# sandh.net
KiCad netlist of a schematic drawn in EAGLE
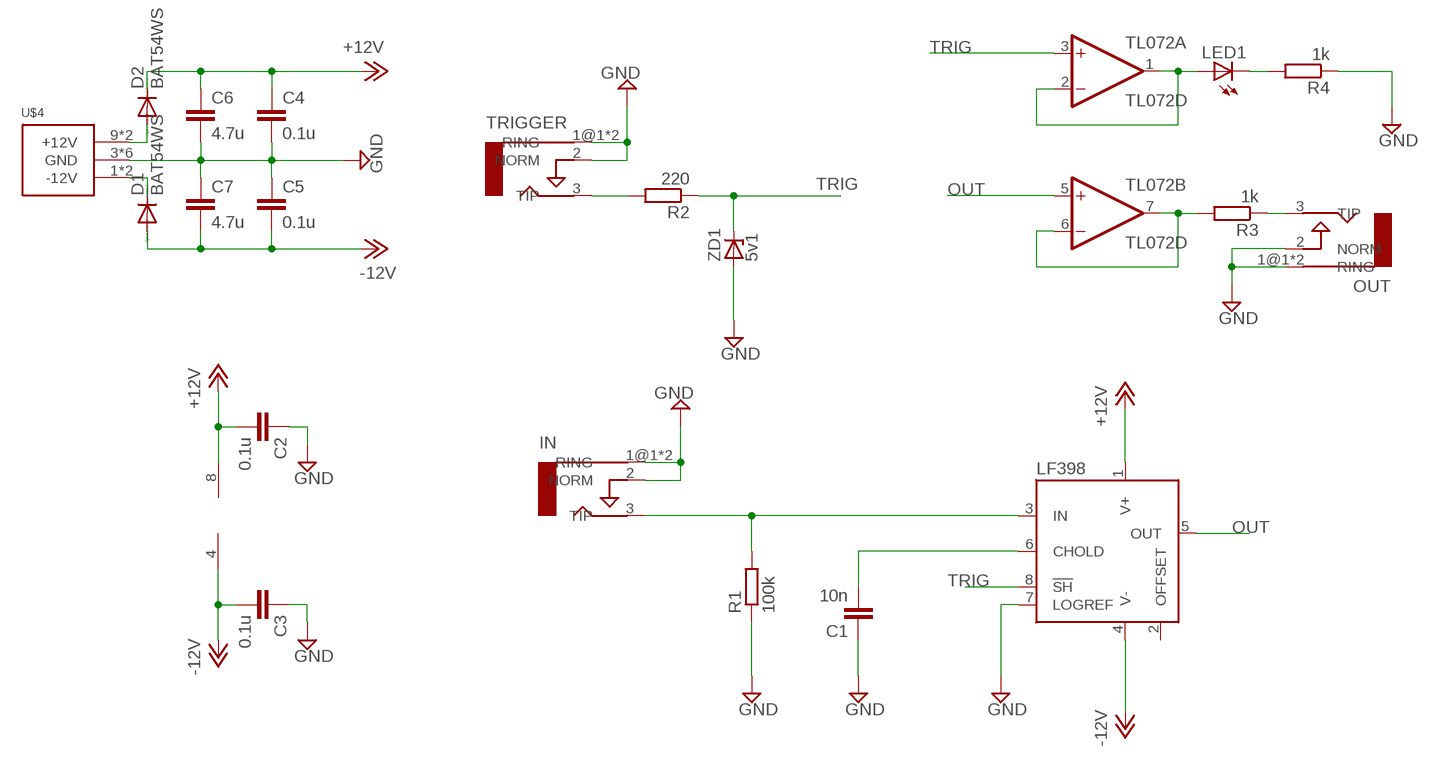
[diagram p0: schematic, sheet 1]

(export (version "E")
  (design (tool "Eeschema 10.0.6"))
  (components
    (comp (ref "C1")
      (value "10n")
      (footprint "eagle-import:C0805")
      (libsource (lib "eagle-import") (part "C-EUC0805"))
    )
    (comp (ref "C2")
      (value "0.1u")
      (footprint "eagle-import:C0805")
      (libsource (lib "eagle-import") (part "C-EUC0805"))
    )
    (comp (ref "C3")
      (value "0.1u")
      (footprint "eagle-import:C0805")
      (libsource (lib "eagle-import") (part "C-EUC0805"))
    )
    (comp (ref "C4")
      (value "0.1u")
      (footprint "eagle-import:C0805")
      (libsource (lib "eagle-import") (part "C-EUC0805"))
    )
    (comp (ref "C5")
      (value "0.1u")
      (footprint "eagle-import:C0805")
      (libsource (lib "eagle-import") (part "C-EUC0805"))
    )
    (comp (ref "C6")
      (value "4.7u")
      (footprint "eagle-import:C0805")
      (libsource (lib "eagle-import") (part "C-EUC0805"))
    )
    (comp (ref "C7")
      (value "4.7u")
      (footprint "eagle-import:C0805")
      (libsource (lib "eagle-import") (part "C-EUC0805"))
    )
    (comp (ref "D1")
      (value "BAT54WS")
      (footprint "eagle-import:SOD323-W")
      (libsource (lib "eagle-import") (part "DIODE-SOD323-W"))
    )
    (comp (ref "D2")
      (value "BAT54WS")
      (footprint "eagle-import:SOD323-W")
      (libsource (lib "eagle-import") (part "DIODE-SOD323-W"))
    )
    (comp (ref "IN")
      (value "AUDIO-JACKERTHENVAR")
      (footprint "eagle-import:ERTHENVAR-JACK")
      (libsource (lib "eagle-import") (part "AUDIO-JACKERTHENVAR"))
    )
    (comp (ref "LED1")
      (value "LEDCHIP-LED0805")
      (footprint "eagle-import:CHIP-LED0805")
      (libsource (lib "eagle-import") (part "LEDCHIP-LED0805"))
    )
    (comp (ref "LF398")
      (value "LF398AN")
      (footprint "eagle-import:DIL08")
      (libsource (lib "eagle-import") (part "LF398AN"))
    )
    (comp (ref "OUT")
      (value "AUDIO-JACKERTHENVAR")
      (footprint "eagle-import:ERTHENVAR-JACK")
      (libsource (lib "eagle-import") (part "AUDIO-JACKERTHENVAR"))
    )
    (comp (ref "R1")
      (value "100k")
      (footprint "eagle-import:R0805")
      (libsource (lib "eagle-import") (part "R-EU_R0805"))
    )
    (comp (ref "R2")
      (value "220")
      (footprint "eagle-import:R0805")
      (libsource (lib "eagle-import") (part "R-EU_R0805"))
    )
    (comp (ref "R3")
      (value "1k")
      (footprint "eagle-import:R0805")
      (libsource (lib "eagle-import") (part "R-EU_R0805"))
    )
    (comp (ref "R4")
      (value "1k")
      (footprint "eagle-import:R0805")
      (libsource (lib "eagle-import") (part "R-EU_R0805"))
    )
    (comp (ref "TL072")
      (value "TL072D")
      (footprint "eagle-import:SO08")
      (libsource (lib "eagle-import") (part "TL072D"))
    )
    (comp (ref "TRIGGER")
      (value "AUDIO-JACKERTHENVAR")
      (footprint "eagle-import:ERTHENVAR-JACK")
      (libsource (lib "eagle-import") (part "AUDIO-JACKERTHENVAR"))
    )
    (comp (ref "U$4")
      (value "POWER_SIMPLE10")
      (footprint "eagle-import:POWER_10")
      (libsource (lib "eagle-import") (part "POWER_SIMPLE10"))
    )
    (comp (ref "ZD1")
      (value "5v1")
      (footprint "eagle-import:ZDIO-2.5")
      (libsource (lib "eagle-import") (part "ZENER-DIODEZD-2.5"))
    )
  )
  (nets
    (net (code "1") (name "+12V") (class "Default")
      (node (ref "C2") (pin "2") (pinfunction "2_2") (pintype "passive"))
      (node (ref "C4") (pin "1") (pinfunction "1_1") (pintype "passive"))
      (node (ref "C6") (pin "1") (pinfunction "1_1") (pintype "passive"))
      (node (ref "D2") (pin "C") (pinfunction "C_C") (pintype "passive"))
      (node (ref "LF398") (pin "1") (pinfunction "V+_1") (pintype "power_in"))
      (node (ref "TL072") (pin "8") (pinfunction "V+_8") (pintype "power_in"))
    )
    (net (code "2") (name "-12V") (class "Default")
      (node (ref "C3") (pin "2") (pinfunction "2_2") (pintype "passive"))
      (node (ref "C5") (pin "2") (pinfunction "2_2") (pintype "passive"))
      (node (ref "C7") (pin "2") (pinfunction "2_2") (pintype "passive"))
      (node (ref "D1") (pin "A") (pinfunction "A_A") (pintype "passive"))
      (node (ref "LF398") (pin "4") (pinfunction "V-_4") (pintype "power_in"))
      (node (ref "TL072") (pin "4") (pinfunction "V-_4") (pintype "power_in"))
    )
    (net (code "3") (name "/OUT") (class "Default")
      (node (ref "LF398") (pin "5") (pinfunction "OUT_5") (pintype "output"))
      (node (ref "TL072") (pin "5") (pinfunction "+IN_5") (pintype "input"))
    )
    (net (code "4") (name "/TRIG") (class "Default")
      (node (ref "LF398") (pin "8") (pinfunction "~{SH}_8") (pintype "input"))
      (node (ref "R2") (pin "1") (pinfunction "1_1") (pintype "passive"))
      (node (ref "TL072") (pin "3") (pinfunction "+IN_3") (pintype "input"))
      (node (ref "ZD1") (pin "C") (pinfunction "C_C") (pintype "passive"))
    )
    (net (code "5") (name "GND") (class "Default")
      (node (ref "C1") (pin "1") (pinfunction "1_1") (pintype "passive"))
      (node (ref "C2") (pin "1") (pinfunction "1_1") (pintype "passive"))
      (node (ref "C3") (pin "1") (pinfunction "1_1") (pintype "passive"))
      (node (ref "C4") (pin "2") (pinfunction "2_2") (pintype "passive"))
      (node (ref "C5") (pin "1") (pinfunction "1_1") (pintype "passive"))
      (node (ref "C6") (pin "2") (pinfunction "2_2") (pintype "passive"))
      (node (ref "C7") (pin "1") (pinfunction "1_1") (pintype "passive"))
      (node (ref "IN") (pin "1@1") (pinfunction "RING_1@1") (pintype "bidirectional"))
      (node (ref "IN") (pin "1@2") (pinfunction "RING_1@2") (pintype "bidirectional"))
      (node (ref "IN") (pin "2") (pinfunction "NORM_2") (pintype "bidirectional"))
      (node (ref "LF398") (pin "7") (pinfunction "LOGREF_7") (pintype "power_in"))
      (node (ref "OUT") (pin "1@1") (pinfunction "RING_1@1") (pintype "bidirectional"))
      (node (ref "OUT") (pin "1@2") (pinfunction "RING_1@2") (pintype "bidirectional"))
      (node (ref "OUT") (pin "2") (pinfunction "NORM_2") (pintype "bidirectional"))
      (node (ref "R1") (pin "1") (pinfunction "1_1") (pintype "passive"))
      (node (ref "R4") (pin "1") (pinfunction "1_1") (pintype "passive"))
      (node (ref "TRIGGER") (pin "1@1") (pinfunction "RING_1@1") (pintype "bidirectional"))
      (node (ref "TRIGGER") (pin "1@2") (pinfunction "RING_1@2") (pintype "bidirectional"))
      (node (ref "TRIGGER") (pin "2") (pinfunction "NORM_2") (pintype "bidirectional"))
      (node (ref "U$4") (pin "3") (pinfunction "GND_3") (pintype "bidirectional"))
      (node (ref "U$4") (pin "4") (pinfunction "GND_4") (pintype "bidirectional"))
      (node (ref "U$4") (pin "5") (pinfunction "GND_5") (pintype "bidirectional"))
      (node (ref "U$4") (pin "6") (pinfunction "GND_6") (pintype "bidirectional"))
      (node (ref "U$4") (pin "7") (pinfunction "GND_7") (pintype "bidirectional"))
      (node (ref "U$4") (pin "8") (pinfunction "GND_8") (pintype "bidirectional"))
      (node (ref "ZD1") (pin "A") (pinfunction "A_A") (pintype "passive"))
    )
    (net (code "6") (name "Net-(D1-PadC)") (class "Default")
      (node (ref "D1") (pin "C") (pinfunction "C_C") (pintype "passive"))
      (node (ref "U$4") (pin "1") (pinfunction "-12V_1") (pintype "bidirectional"))
      (node (ref "U$4") (pin "2") (pinfunction "-12V_2") (pintype "bidirectional"))
    )
    (net (code "7") (name "Net-(D2-PadA)") (class "Default")
      (node (ref "D2") (pin "A") (pinfunction "A_A") (pintype "passive"))
      (node (ref "U$4") (pin "10") (pinfunction "+12V_10") (pintype "bidirectional"))
      (node (ref "U$4") (pin "9") (pinfunction "+12V_9") (pintype "bidirectional"))
    )
    (net (code "8") (name "Net-(IN-TIP)") (class "Default")
      (node (ref "IN") (pin "3") (pinfunction "TIP_3") (pintype "bidirectional"))
      (node (ref "LF398") (pin "3") (pinfunction "IN_3") (pintype "input"))
      (node (ref "R1") (pin "2") (pinfunction "2_2") (pintype "passive"))
    )
    (net (code "9") (name "Net-(LED1-PadC)") (class "Default")
      (node (ref "LED1") (pin "C") (pinfunction "C_C") (pintype "passive"))
      (node (ref "R4") (pin "2") (pinfunction "2_2") (pintype "passive"))
    )
    (net (code "10") (name "Net-(LF398-CHOLD)") (class "Default")
      (node (ref "C1") (pin "2") (pinfunction "2_2") (pintype "passive"))
      (node (ref "LF398") (pin "6") (pinfunction "CHOLD_6") (pintype "passive"))
    )
    (net (code "11") (name "Net-(OUT-TIP)") (class "Default")
      (node (ref "OUT") (pin "3") (pinfunction "TIP_3") (pintype "bidirectional"))
      (node (ref "R3") (pin "1") (pinfunction "1_1") (pintype "passive"))
    )
    (net (code "12") (name "Net-(TL072A--IN)") (class "Default")
      (node (ref "LED1") (pin "A") (pinfunction "A_A") (pintype "passive"))
      (node (ref "TL072") (pin "1") (pinfunction "OUT_1") (pintype "output"))
      (node (ref "TL072") (pin "2") (pinfunction "-IN_2") (pintype "input"))
    )
    (net (code "13") (name "Net-(TL072B--IN)") (class "Default")
      (node (ref "R3") (pin "2") (pinfunction "2_2") (pintype "passive"))
      (node (ref "TL072") (pin "6") (pinfunction "-IN_6") (pintype "input"))
      (node (ref "TL072") (pin "7") (pinfunction "OUT_7") (pintype "output"))
    )
    (net (code "14") (name "Net-(TRIGGER-TIP)") (class "Default")
      (node (ref "R2") (pin "2") (pinfunction "2_2") (pintype "passive"))
      (node (ref "TRIGGER") (pin "3") (pinfunction "TIP_3") (pintype "bidirectional"))
    )
    (net (code "15") (name "unconnected-(LF398-OFFSET-Pad2)") (class "Default")
      (node (ref "LF398") (pin "2") (pinfunction "OFFSET_2") (pintype "input"))
    )
  )
)
